# controller.net
KiCad netlist of a schematic drawn in EAGLE
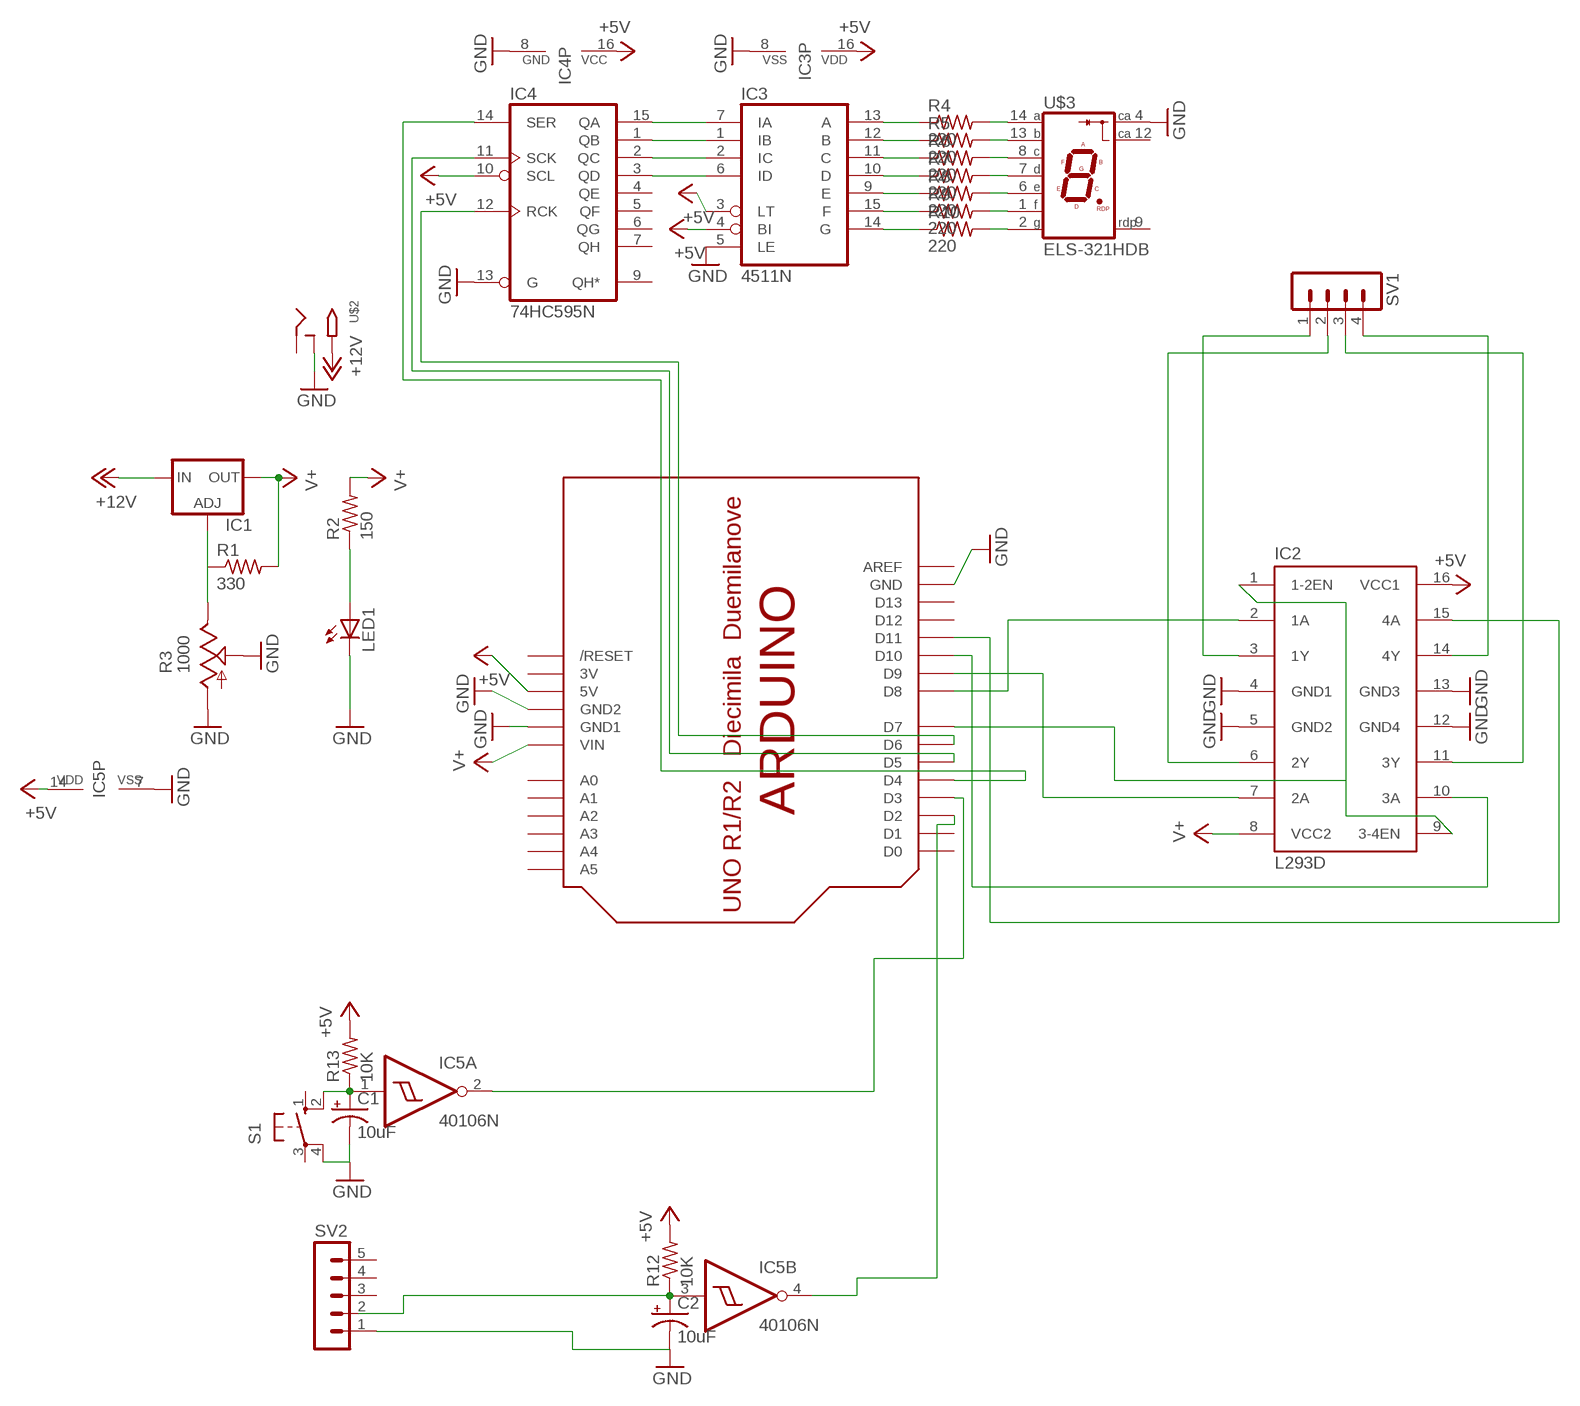
[diagram p0: schematic, sheet 1]

(export (version "E")
  (design (tool "Eeschema 10.0.6"))
  (components
    (comp (ref "C1")
      (value "10uF")
      (footprint "eagle-import:E2,5-5")
      (libsource (lib "eagle-import") (part "CPOL-USE2.5-5"))
    )
    (comp (ref "C2")
      (value "10uF")
      (footprint "eagle-import:E2,5-5")
      (libsource (lib "eagle-import") (part "CPOL-USE2.5-5"))
    )
    (comp (ref "IC1")
      (value "LM317TS")
      (footprint "eagle-import:317TS")
      (libsource (lib "eagle-import") (part "LM317TS"))
    )
    (comp (ref "IC2")
      (value "L293D")
      (footprint "eagle-import:DIL16")
      (libsource (lib "eagle-import") (part "L293D"))
    )
    (comp (ref "IC3")
      (value "4511N")
      (footprint "eagle-import:DIL16")
      (libsource (lib "eagle-import") (part "4511N"))
    )
    (comp (ref "IC4")
      (value "74HC595N")
      (footprint "eagle-import:DIL16")
      (libsource (lib "eagle-import") (part "74595NHC"))
    )
    (comp (ref "IC5")
      (value "40106N")
      (footprint "eagle-import:DIL14")
      (libsource (lib "eagle-import") (part "40106N"))
    )
    (comp (ref "LED1")
      (value "LED5MM")
      (footprint "eagle-import:LED5MM")
      (libsource (lib "eagle-import") (part "LED5MM"))
    )
    (comp (ref "R1")
      (value "330")
      (footprint "eagle-import:0207_10")
      (libsource (lib "eagle-import") (part "resistor_R-US_0207/10"))
    )
    (comp (ref "R2")
      (value "150")
      (footprint "eagle-import:0207_10")
      (libsource (lib "eagle-import") (part "resistor_R-US_0207/10"))
    )
    (comp (ref "R3")
      (value "1000")
      (footprint "eagle-import:LI10")
      (libsource (lib "eagle-import") (part "TRIM_US-LI10"))
    )
    (comp (ref "R4")
      (value "220")
      (footprint "eagle-import:0207_7")
      (libsource (lib "eagle-import") (part "R-US_0207/7"))
    )
    (comp (ref "R5")
      (value "220")
      (footprint "eagle-import:0207_7")
      (libsource (lib "eagle-import") (part "R-US_0207/7"))
    )
    (comp (ref "R6")
      (value "220")
      (footprint "eagle-import:0207_7")
      (libsource (lib "eagle-import") (part "R-US_0207/7"))
    )
    (comp (ref "R7")
      (value "220")
      (footprint "eagle-import:0207_7")
      (libsource (lib "eagle-import") (part "R-US_0207/7"))
    )
    (comp (ref "R8")
      (value "220")
      (footprint "eagle-import:0207_7")
      (libsource (lib "eagle-import") (part "R-US_0207/7"))
    )
    (comp (ref "R9")
      (value "220")
      (footprint "eagle-import:0207_7")
      (libsource (lib "eagle-import") (part "R-US_0207/7"))
    )
    (comp (ref "R10")
      (value "220")
      (footprint "eagle-import:0207_7")
      (libsource (lib "eagle-import") (part "R-US_0207/7"))
    )
    (comp (ref "R12")
      (value "10K")
      (footprint "eagle-import:0207_7")
      (libsource (lib "eagle-import") (part "R-US_0207/7"))
    )
    (comp (ref "R13")
      (value "10K")
      (footprint "eagle-import:0207_7")
      (libsource (lib "eagle-import") (part "R-US_0207/7"))
    )
    (comp (ref "S1")
      (value "10-XX")
      (footprint "eagle-import:B3F-10XX")
      (fields (field (name "MPN") "B3F-1000"))
      (libsource (lib "eagle-import") (part "10-XX"))
    )
    (comp (ref "SV1")
      (value "MA04-1")
      (footprint "eagle-import:MA04-1")
      (libsource (lib "eagle-import") (part "MA04-1"))
    )
    (comp (ref "SV2")
      (value "MA05-1")
      (footprint "eagle-import:MA05-1")
      (libsource (lib "eagle-import") (part "MA05-1"))
    )
    (comp (ref "U$1")
      (value "ARDUINO-BPLACE")
      (footprint "eagle-import:ARDUINO-BPLACE")
      (libsource (lib "eagle-import") (part "ARDUINO-BPLACE"))
    )
    (comp (ref "U$2")
      (value "2.1MMJACKTHM")
      (footprint "eagle-import:PJ-102A")
      (libsource (lib "eagle-import") (part "2.1MMJACKTHM"))
    )
    (comp (ref "U$3")
      (value "ELS-321HDB")
      (footprint "eagle-import:ELS-321HDB")
      (libsource (lib "eagle-import") (part "ELS-321HDB"))
    )
  )
  (nets
    (net (code "1") (name "+5V") (class "Default")
      (node (ref "IC2") (pin "16") (pinfunction "VCC1_16") (pintype "power_in"))
      (node (ref "IC3") (pin "16") (pinfunction "VDD_16") (pintype "power_in"))
      (node (ref "IC3") (pin "3") (pinfunction "LT_3") (pintype "input"))
      (node (ref "IC3") (pin "4") (pinfunction "BI_4") (pintype "input"))
      (node (ref "IC4") (pin "10") (pinfunction "SCL_10") (pintype "input"))
      (node (ref "IC4") (pin "16") (pinfunction "VCC_16") (pintype "power_in"))
      (node (ref "IC5") (pin "14") (pinfunction "VDD_14") (pintype "power_in"))
      (node (ref "R12") (pin "2") (pinfunction "2_2") (pintype "passive"))
      (node (ref "R13") (pin "2") (pinfunction "2_2") (pintype "passive"))
      (node (ref "U$1") (pin "5V") (pinfunction "5V_5V") (pintype "power_in"))
    )
    (net (code "2") (name "+12V") (class "Default")
      (node (ref "IC1") (pin "3") (pinfunction "IN_3") (pintype "input"))
      (node (ref "U$2") (pin "TIP") (pinfunction "TIP_TIP") (pintype "bidirectional"))
    )
    (net (code "3") (name "/3V") (class "Default")
      (node (ref "U$1") (pin "3V") (pinfunction "3V_3V") (pintype "power_in"))
    )
    (net (code "4") (name "GND") (class "Default")
      (node (ref "C1") (pin "-") (pinfunction "-_-") (pintype "passive"))
      (node (ref "C2") (pin "-") (pinfunction "-_-") (pintype "passive"))
      (node (ref "IC2") (pin "12") (pinfunction "GND4_12") (pintype "power_in"))
      (node (ref "IC2") (pin "13") (pinfunction "GND3_13") (pintype "power_in"))
      (node (ref "IC2") (pin "4") (pinfunction "GND1_4") (pintype "power_in"))
      (node (ref "IC2") (pin "5") (pinfunction "GND2_5") (pintype "power_in"))
      (node (ref "IC3") (pin "5") (pinfunction "LE_5") (pintype "input"))
      (node (ref "IC3") (pin "8") (pinfunction "VSS_8") (pintype "power_in"))
      (node (ref "IC4") (pin "13") (pinfunction "G_13") (pintype "input"))
      (node (ref "IC4") (pin "8") (pinfunction "GND_8") (pintype "power_in"))
      (node (ref "IC5") (pin "7") (pinfunction "VSS_7") (pintype "power_in"))
      (node (ref "LED1") (pin "K") (pinfunction "C_K") (pintype "passive"))
      (node (ref "R3") (pin "A") (pinfunction "A_A") (pintype "passive"))
      (node (ref "R3") (pin "S") (pinfunction "S_S") (pintype "passive"))
      (node (ref "S1") (pin "4") (pinfunction "P1_4") (pintype "passive"))
      (node (ref "SV2") (pin "1") (pinfunction "1_1") (pintype "passive"))
      (node (ref "U$1") (pin "GND") (pinfunction "GND_GND") (pintype "power_in"))
      (node (ref "U$1") (pin "GND1") (pinfunction "GND1_GND1") (pintype "power_in"))
      (node (ref "U$1") (pin "GND2") (pinfunction "GND2_GND2") (pintype "power_in"))
      (node (ref "U$2") (pin "RING_SW") (pinfunction "RING_SW_RING_SW") (pintype "bidirectional"))
      (node (ref "U$3") (pin "4") (pinfunction "C_4") (pintype "passive"))
    )
    (net (code "5") (name "Net-(IC1-ADJ)") (class "Default")
      (node (ref "IC1") (pin "1") (pinfunction "ADJ_1") (pintype "input"))
      (node (ref "R1") (pin "1") (pinfunction "1_1") (pintype "passive"))
      (node (ref "R3") (pin "E") (pinfunction "E_E") (pintype "passive"))
    )
    (net (code "6") (name "Net-(IC2-1-2EN)") (class "Default")
      (node (ref "IC2") (pin "1") (pinfunction "1-2EN_1") (pintype "input"))
      (node (ref "IC2") (pin "9") (pinfunction "3-4EN_9") (pintype "input"))
      (node (ref "U$1") (pin "D7") (pinfunction "D7_D7") (pintype "bidirectional"))
    )
    (net (code "7") (name "Net-(IC2-1A)") (class "Default")
      (node (ref "IC2") (pin "2") (pinfunction "1A_2") (pintype "input"))
      (node (ref "U$1") (pin "D8") (pinfunction "D8_D8") (pintype "bidirectional"))
    )
    (net (code "8") (name "Net-(IC2-1Y)") (class "Default")
      (node (ref "IC2") (pin "3") (pinfunction "1Y_3") (pintype "output"))
      (node (ref "SV1") (pin "1") (pinfunction "1_1") (pintype "passive"))
    )
    (net (code "9") (name "Net-(IC2-2A)") (class "Default")
      (node (ref "IC2") (pin "7") (pinfunction "2A_7") (pintype "input"))
      (node (ref "U$1") (pin "D9") (pinfunction "D9_D9") (pintype "bidirectional"))
    )
    (net (code "10") (name "Net-(IC2-2Y)") (class "Default")
      (node (ref "IC2") (pin "6") (pinfunction "2Y_6") (pintype "output"))
      (node (ref "SV1") (pin "2") (pinfunction "2_2") (pintype "passive"))
    )
    (net (code "11") (name "Net-(IC2-3A)") (class "Default")
      (node (ref "IC2") (pin "10") (pinfunction "3A_10") (pintype "input"))
      (node (ref "U$1") (pin "D10") (pinfunction "D10_D10") (pintype "bidirectional"))
    )
    (net (code "12") (name "Net-(IC2-3Y)") (class "Default")
      (node (ref "IC2") (pin "11") (pinfunction "3Y_11") (pintype "output"))
      (node (ref "SV1") (pin "3") (pinfunction "3_3") (pintype "passive"))
    )
    (net (code "13") (name "Net-(IC2-4A)") (class "Default")
      (node (ref "IC2") (pin "15") (pinfunction "4A_15") (pintype "input"))
      (node (ref "U$1") (pin "D11") (pinfunction "D11_D11") (pintype "bidirectional"))
    )
    (net (code "14") (name "Net-(IC2-4Y)") (class "Default")
      (node (ref "IC2") (pin "14") (pinfunction "4Y_14") (pintype "output"))
      (node (ref "SV1") (pin "4") (pinfunction "4_4") (pintype "passive"))
    )
    (net (code "15") (name "Net-(IC3A-A)") (class "Default")
      (node (ref "IC3") (pin "13") (pinfunction "A_13") (pintype "output"))
      (node (ref "R4") (pin "1") (pinfunction "1_1") (pintype "passive"))
    )
    (net (code "16") (name "Net-(IC3A-B)") (class "Default")
      (node (ref "IC3") (pin "12") (pinfunction "B_12") (pintype "output"))
      (node (ref "R5") (pin "1") (pinfunction "1_1") (pintype "passive"))
    )
    (net (code "17") (name "Net-(IC3A-C)") (class "Default")
      (node (ref "IC3") (pin "11") (pinfunction "C_11") (pintype "output"))
      (node (ref "R6") (pin "1") (pinfunction "1_1") (pintype "passive"))
    )
    (net (code "18") (name "Net-(IC3A-D)") (class "Default")
      (node (ref "IC3") (pin "10") (pinfunction "D_10") (pintype "output"))
      (node (ref "R7") (pin "1") (pinfunction "1_1") (pintype "passive"))
    )
    (net (code "19") (name "Net-(IC3A-E)") (class "Default")
      (node (ref "IC3") (pin "9") (pinfunction "E_9") (pintype "output"))
      (node (ref "R8") (pin "1") (pinfunction "1_1") (pintype "passive"))
    )
    (net (code "20") (name "Net-(IC3A-F)") (class "Default")
      (node (ref "IC3") (pin "15") (pinfunction "F_15") (pintype "output"))
      (node (ref "R9") (pin "1") (pinfunction "1_1") (pintype "passive"))
    )
    (net (code "21") (name "Net-(IC3A-G)") (class "Default")
      (node (ref "IC3") (pin "14") (pinfunction "G_14") (pintype "output"))
      (node (ref "R10") (pin "1") (pinfunction "1_1") (pintype "passive"))
    )
    (net (code "22") (name "Net-(IC3A-IA)") (class "Default")
      (node (ref "IC3") (pin "7") (pinfunction "IA_7") (pintype "input"))
      (node (ref "IC4") (pin "15") (pinfunction "QA_15") (pintype "tri_state"))
    )
    (net (code "23") (name "Net-(IC3A-IB)") (class "Default")
      (node (ref "IC3") (pin "1") (pinfunction "IB_1") (pintype "input"))
      (node (ref "IC4") (pin "1") (pinfunction "QB_1") (pintype "tri_state"))
    )
    (net (code "24") (name "Net-(IC3A-IC)") (class "Default")
      (node (ref "IC3") (pin "2") (pinfunction "IC_2") (pintype "input"))
      (node (ref "IC4") (pin "2") (pinfunction "QC_2") (pintype "tri_state"))
    )
    (net (code "25") (name "Net-(IC3A-ID)") (class "Default")
      (node (ref "IC3") (pin "6") (pinfunction "ID_6") (pintype "input"))
      (node (ref "IC4") (pin "3") (pinfunction "QD_3") (pintype "tri_state"))
    )
    (net (code "26") (name "Net-(IC4A-RCK)") (class "Default")
      (node (ref "IC4") (pin "12") (pinfunction "RCK_12") (pintype "input"))
      (node (ref "U$1") (pin "D6") (pinfunction "D6_D6") (pintype "bidirectional"))
    )
    (net (code "27") (name "Net-(IC4A-SCK)") (class "Default")
      (node (ref "IC4") (pin "11") (pinfunction "SCK_11") (pintype "input"))
      (node (ref "U$1") (pin "D5") (pinfunction "D5_D5") (pintype "bidirectional"))
    )
    (net (code "28") (name "Net-(IC4A-SER)") (class "Default")
      (node (ref "IC4") (pin "14") (pinfunction "SER_14") (pintype "input"))
      (node (ref "U$1") (pin "D4") (pinfunction "D4_D4") (pintype "bidirectional"))
    )
    (net (code "29") (name "Net-(IC5A-I)") (class "Default")
      (node (ref "C1") (pin "+") (pinfunction "+_+") (pintype "passive"))
      (node (ref "IC5") (pin "1") (pinfunction "I_1") (pintype "input"))
      (node (ref "R13") (pin "1") (pinfunction "1_1") (pintype "passive"))
      (node (ref "S1") (pin "2") (pinfunction "S1_2") (pintype "passive"))
    )
    (net (code "30") (name "Net-(IC5A-O)") (class "Default")
      (node (ref "IC5") (pin "2") (pinfunction "O_2") (pintype "output"))
      (node (ref "U$1") (pin "D3") (pinfunction "D3_D3") (pintype "bidirectional"))
    )
    (net (code "31") (name "Net-(IC5B-I)") (class "Default")
      (node (ref "C2") (pin "+") (pinfunction "+_+") (pintype "passive"))
      (node (ref "IC5") (pin "3") (pinfunction "I_3") (pintype "input"))
      (node (ref "R12") (pin "1") (pinfunction "1_1") (pintype "passive"))
      (node (ref "SV2") (pin "2") (pinfunction "2_2") (pintype "passive"))
    )
    (net (code "32") (name "Net-(IC5B-O)") (class "Default")
      (node (ref "IC5") (pin "4") (pinfunction "O_4") (pintype "output"))
      (node (ref "U$1") (pin "D2") (pinfunction "D2_D2") (pintype "bidirectional"))
    )
    (net (code "33") (name "Net-(LED1-PadA)") (class "Default")
      (node (ref "LED1") (pin "A") (pinfunction "A_A") (pintype "passive"))
      (node (ref "R2") (pin "1") (pinfunction "1_1") (pintype "passive"))
    )
    (net (code "34") (name "Net-(R6-Pad2)") (class "Default")
      (node (ref "R6") (pin "2") (pinfunction "2_2") (pintype "passive"))
      (node (ref "U$3") (pin "8") (pinfunction "C_8") (pintype "passive"))
    )
    (net (code "35") (name "Net-(U$3-A)") (class "Default")
      (node (ref "R4") (pin "2") (pinfunction "2_2") (pintype "passive"))
      (node (ref "U$3") (pin "14") (pinfunction "A_14") (pintype "passive"))
    )
    (net (code "36") (name "Net-(U$3-B)") (class "Default")
      (node (ref "R5") (pin "2") (pinfunction "2_2") (pintype "passive"))
      (node (ref "U$3") (pin "13") (pinfunction "B_13") (pintype "passive"))
    )
    (net (code "37") (name "Net-(U$3-D)") (class "Default")
      (node (ref "R7") (pin "2") (pinfunction "2_2") (pintype "passive"))
      (node (ref "U$3") (pin "7") (pinfunction "D_7") (pintype "passive"))
    )
    (net (code "38") (name "Net-(U$3-E)") (class "Default")
      (node (ref "R8") (pin "2") (pinfunction "2_2") (pintype "passive"))
      (node (ref "U$3") (pin "6") (pinfunction "E_6") (pintype "passive"))
    )
    (net (code "39") (name "Net-(U$3-F)") (class "Default")
      (node (ref "R9") (pin "2") (pinfunction "2_2") (pintype "passive"))
      (node (ref "U$3") (pin "1") (pinfunction "F_1") (pintype "passive"))
    )
    (net (code "40") (name "Net-(U$3-G)") (class "Default")
      (node (ref "R10") (pin "2") (pinfunction "2_2") (pintype "passive"))
      (node (ref "U$3") (pin "2") (pinfunction "G_2") (pintype "passive"))
    )
    (net (code "41") (name "V+") (class "Default")
      (node (ref "IC1") (pin "2") (pinfunction "OUT_2") (pintype "passive"))
      (node (ref "IC2") (pin "8") (pinfunction "VCC2_8") (pintype "power_in"))
      (node (ref "R1") (pin "2") (pinfunction "2_2") (pintype "passive"))
      (node (ref "R2") (pin "2") (pinfunction "2_2") (pintype "passive"))
      (node (ref "U$1") (pin "VIN") (pinfunction "VIN_VIN") (pintype "power_in"))
    )
    (net (code "42") (name "unconnected-(IC4A-QE-Pad4)") (class "Default")
      (node (ref "IC4") (pin "4") (pinfunction "QE_4") (pintype "tri_state"))
    )
    (net (code "43") (name "unconnected-(IC4A-QF-Pad5)") (class "Default")
      (node (ref "IC4") (pin "5") (pinfunction "QF_5") (pintype "tri_state"))
    )
    (net (code "44") (name "unconnected-(IC4A-QG-Pad6)") (class "Default")
      (node (ref "IC4") (pin "6") (pinfunction "QG_6") (pintype "tri_state"))
    )
    (net (code "45") (name "unconnected-(IC4A-QH*-Pad9)") (class "Default")
      (node (ref "IC4") (pin "9") (pinfunction "QH*_9") (pintype "tri_state"))
    )
    (net (code "46") (name "unconnected-(IC4A-QH-Pad7)") (class "Default")
      (node (ref "IC4") (pin "7") (pinfunction "QH_7") (pintype "tri_state"))
    )
    (net (code "47") (name "unconnected-(S1-P-Pad3)") (class "Default")
      (node (ref "S1") (pin "3") (pinfunction "P_3") (pintype "passive"))
    )
    (net (code "48") (name "unconnected-(S1-S-Pad1)") (class "Default")
      (node (ref "S1") (pin "1") (pinfunction "S_1") (pintype "passive"))
    )
    (net (code "49") (name "unconnected-(SV2-Pad3)") (class "Default")
      (node (ref "SV2") (pin "3") (pinfunction "3_3") (pintype "passive"))
    )
    (net (code "50") (name "unconnected-(SV2-Pad4)") (class "Default")
      (node (ref "SV2") (pin "4") (pinfunction "4_4") (pintype "passive"))
    )
    (net (code "51") (name "unconnected-(SV2-Pad5)") (class "Default")
      (node (ref "SV2") (pin "5") (pinfunction "5_5") (pintype "passive"))
    )
    (net (code "52") (name "unconnected-(U$1-PadA0)") (class "Default")
      (node (ref "U$1") (pin "A0") (pinfunction "A0_A0") (pintype "bidirectional"))
    )
    (net (code "53") (name "unconnected-(U$1-PadA1)") (class "Default")
      (node (ref "U$1") (pin "A1") (pinfunction "A1_A1") (pintype "bidirectional"))
    )
    (net (code "54") (name "unconnected-(U$1-PadA2)") (class "Default")
      (node (ref "U$1") (pin "A2") (pinfunction "A2_A2") (pintype "bidirectional"))
    )
    (net (code "55") (name "unconnected-(U$1-PadA3)") (class "Default")
      (node (ref "U$1") (pin "A3") (pinfunction "A3_A3") (pintype "bidirectional"))
    )
    (net (code "56") (name "unconnected-(U$1-PadA4)") (class "Default")
      (node (ref "U$1") (pin "A4") (pinfunction "A4_A4") (pintype "bidirectional"))
    )
    (net (code "57") (name "unconnected-(U$1-PadA5)") (class "Default")
      (node (ref "U$1") (pin "A5") (pinfunction "A5_A5") (pintype "bidirectional"))
    )
    (net (code "58") (name "unconnected-(U$1-PadAREF)") (class "Default")
      (node (ref "U$1") (pin "AREF") (pinfunction "AREF_AREF") (pintype "bidirectional"))
    )
    (net (code "59") (name "unconnected-(U$1-PadD0)") (class "Default")
      (node (ref "U$1") (pin "D0") (pinfunction "D0_D0") (pintype "bidirectional"))
    )
    (net (code "60") (name "unconnected-(U$1-PadD1)") (class "Default")
      (node (ref "U$1") (pin "D1") (pinfunction "D1_D1") (pintype "bidirectional"))
    )
    (net (code "61") (name "unconnected-(U$1-PadD12)") (class "Default")
      (node (ref "U$1") (pin "D12") (pinfunction "D12_D12") (pintype "bidirectional"))
    )
    (net (code "62") (name "unconnected-(U$1-PadD13)") (class "Default")
      (node (ref "U$1") (pin "D13") (pinfunction "D13_D13") (pintype "bidirectional"))
    )
    (net (code "63") (name "unconnected-(U$1-{slash}RESET-PadRESET)") (class "Default")
      (node (ref "U$1") (pin "RESET") (pinfunction "/RESET_RESET") (pintype "bidirectional"))
    )
    (net (code "64") (name "unconnected-(U$2-PadRING)") (class "Default")
      (node (ref "U$2") (pin "RING") (pinfunction "RING_RING") (pintype "bidirectional"))
    )
    (net (code "65") (name "unconnected-(U$3-C-Pad12)") (class "Default")
      (node (ref "U$3") (pin "12") (pinfunction "C_12") (pintype "passive"))
    )
    (net (code "66") (name "unconnected-(U$3-RDP-Pad9)") (class "Default")
      (node (ref "U$3") (pin "9") (pinfunction "RDP_9") (pintype "passive"))
    )
  )
)
